# Encoder_Sheet.net
KiCad netlist of a schematic drawn in Altium Designer
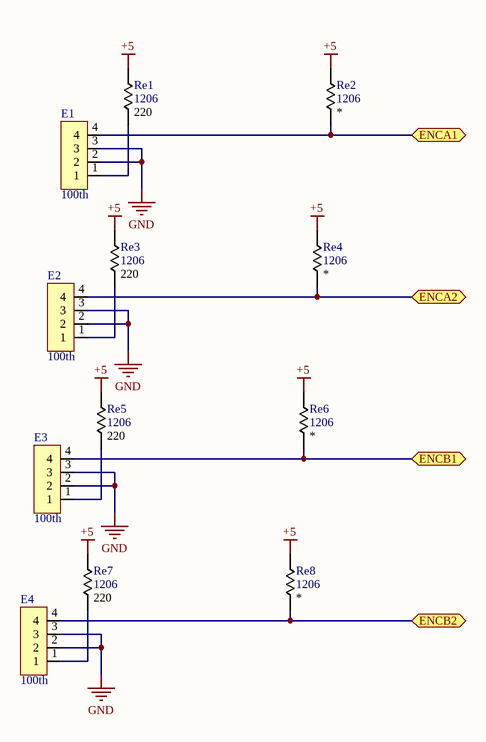
[diagram p0: Encoder_Sheet.SchDoc]

(export (version "E")
  (design (tool "Eeschema 10.0.6"))
  (components
    (comp (ref "E1")
      (value "100th")
      (footprint "pin4header")
      (libsource (lib "pin4header") (part "Pin4Header"))
    )
    (comp (ref "E2")
      (value "100th")
      (footprint "pin4header")
      (libsource (lib "pin4header") (part "Pin4Header"))
    )
    (comp (ref "E3")
      (value "100th")
      (footprint "pin4header")
      (libsource (lib "pin4header") (part "Pin4Header"))
    )
    (comp (ref "E4")
      (value "100th")
      (footprint "pin4header")
      (libsource (lib "pin4header") (part "Pin4Header"))
    )
    (comp (ref "Re1")
      (value "1206")
      (footprint "1206")
      (fields (field (name "ALTIUM_VALUE") "220"))
      (libsource (lib "Res_3_2__1_6") (part "1206"))
    )
    (comp (ref "Re2")
      (value "1206")
      (footprint "1206")
      (fields (field (name "ALTIUM_VALUE") "*"))
      (libsource (lib "Res_3_2__1_6") (part "1206"))
    )
    (comp (ref "Re3")
      (value "1206")
      (footprint "1206")
      (fields (field (name "ALTIUM_VALUE") "220"))
      (libsource (lib "Res_3_2__1_6") (part "1206"))
    )
    (comp (ref "Re4")
      (value "1206")
      (footprint "1206")
      (fields (field (name "ALTIUM_VALUE") "*"))
      (libsource (lib "Res_3_2__1_6") (part "1206"))
    )
    (comp (ref "Re5")
      (value "1206")
      (footprint "1206")
      (fields (field (name "ALTIUM_VALUE") "220"))
      (libsource (lib "Res_3_2__1_6") (part "1206"))
    )
    (comp (ref "Re6")
      (value "1206")
      (footprint "1206")
      (fields (field (name "ALTIUM_VALUE") "*"))
      (libsource (lib "Res_3_2__1_6") (part "1206"))
    )
    (comp (ref "Re7")
      (value "1206")
      (footprint "1206")
      (fields (field (name "ALTIUM_VALUE") "220"))
      (libsource (lib "Res_3_2__1_6") (part "1206"))
    )
    (comp (ref "Re8")
      (value "1206")
      (footprint "1206")
      (fields (field (name "ALTIUM_VALUE") "*"))
      (libsource (lib "Res_3_2__1_6") (part "1206"))
    )
  )
  (nets
    (net (code "1") (name "+5") (class "Default")
      (node (ref "Re1") (pin "2") (pinfunction "2_2") (pintype "passive"))
      (node (ref "Re2") (pin "2") (pinfunction "2_2") (pintype "passive"))
      (node (ref "Re3") (pin "2") (pinfunction "2_2") (pintype "passive"))
      (node (ref "Re4") (pin "2") (pinfunction "2_2") (pintype "passive"))
      (node (ref "Re5") (pin "2") (pinfunction "2_2") (pintype "passive"))
      (node (ref "Re6") (pin "2") (pinfunction "2_2") (pintype "passive"))
      (node (ref "Re7") (pin "2") (pinfunction "2_2") (pintype "passive"))
      (node (ref "Re8") (pin "2") (pinfunction "2_2") (pintype "passive"))
    )
    (net (code "2") (name "/ENCA1") (class "Default")
      (node (ref "E1") (pin "4") (pinfunction "4_4") (pintype "passive"))
      (node (ref "Re2") (pin "1") (pinfunction "1_1") (pintype "passive"))
    )
    (net (code "3") (name "/ENCA2") (class "Default")
      (node (ref "E2") (pin "4") (pinfunction "4_4") (pintype "passive"))
      (node (ref "Re4") (pin "1") (pinfunction "1_1") (pintype "passive"))
    )
    (net (code "4") (name "/ENCB1") (class "Default")
      (node (ref "E3") (pin "4") (pinfunction "4_4") (pintype "passive"))
      (node (ref "Re6") (pin "1") (pinfunction "1_1") (pintype "passive"))
    )
    (net (code "5") (name "/ENCB2") (class "Default")
      (node (ref "E4") (pin "4") (pinfunction "4_4") (pintype "passive"))
      (node (ref "Re8") (pin "1") (pinfunction "1_1") (pintype "passive"))
    )
    (net (code "6") (name "GND") (class "Default")
      (node (ref "E1") (pin "2") (pinfunction "2_2") (pintype "passive"))
      (node (ref "E1") (pin "3") (pinfunction "3_3") (pintype "passive"))
      (node (ref "E2") (pin "2") (pinfunction "2_2") (pintype "passive"))
      (node (ref "E2") (pin "3") (pinfunction "3_3") (pintype "passive"))
      (node (ref "E3") (pin "2") (pinfunction "2_2") (pintype "passive"))
      (node (ref "E3") (pin "3") (pinfunction "3_3") (pintype "passive"))
      (node (ref "E4") (pin "2") (pinfunction "2_2") (pintype "passive"))
      (node (ref "E4") (pin "3") (pinfunction "3_3") (pintype "passive"))
    )
    (net (code "7") (name "Net-(E1-Pad1)") (class "Default")
      (node (ref "E1") (pin "1") (pinfunction "1_1") (pintype "passive"))
      (node (ref "Re1") (pin "1") (pinfunction "1_1") (pintype "passive"))
    )
    (net (code "8") (name "Net-(E2-Pad1)") (class "Default")
      (node (ref "E2") (pin "1") (pinfunction "1_1") (pintype "passive"))
      (node (ref "Re3") (pin "1") (pinfunction "1_1") (pintype "passive"))
    )
    (net (code "9") (name "Net-(E3-Pad1)") (class "Default")
      (node (ref "E3") (pin "1") (pinfunction "1_1") (pintype "passive"))
      (node (ref "Re5") (pin "1") (pinfunction "1_1") (pintype "passive"))
    )
    (net (code "10") (name "Net-(E4-Pad1)") (class "Default")
      (node (ref "E4") (pin "1") (pinfunction "1_1") (pintype "passive"))
      (node (ref "Re7") (pin "1") (pinfunction "1_1") (pintype "passive"))
    )
  )
)
